# SEMAFORO.net
KiCad netlist of a schematic drawn in EAGLE
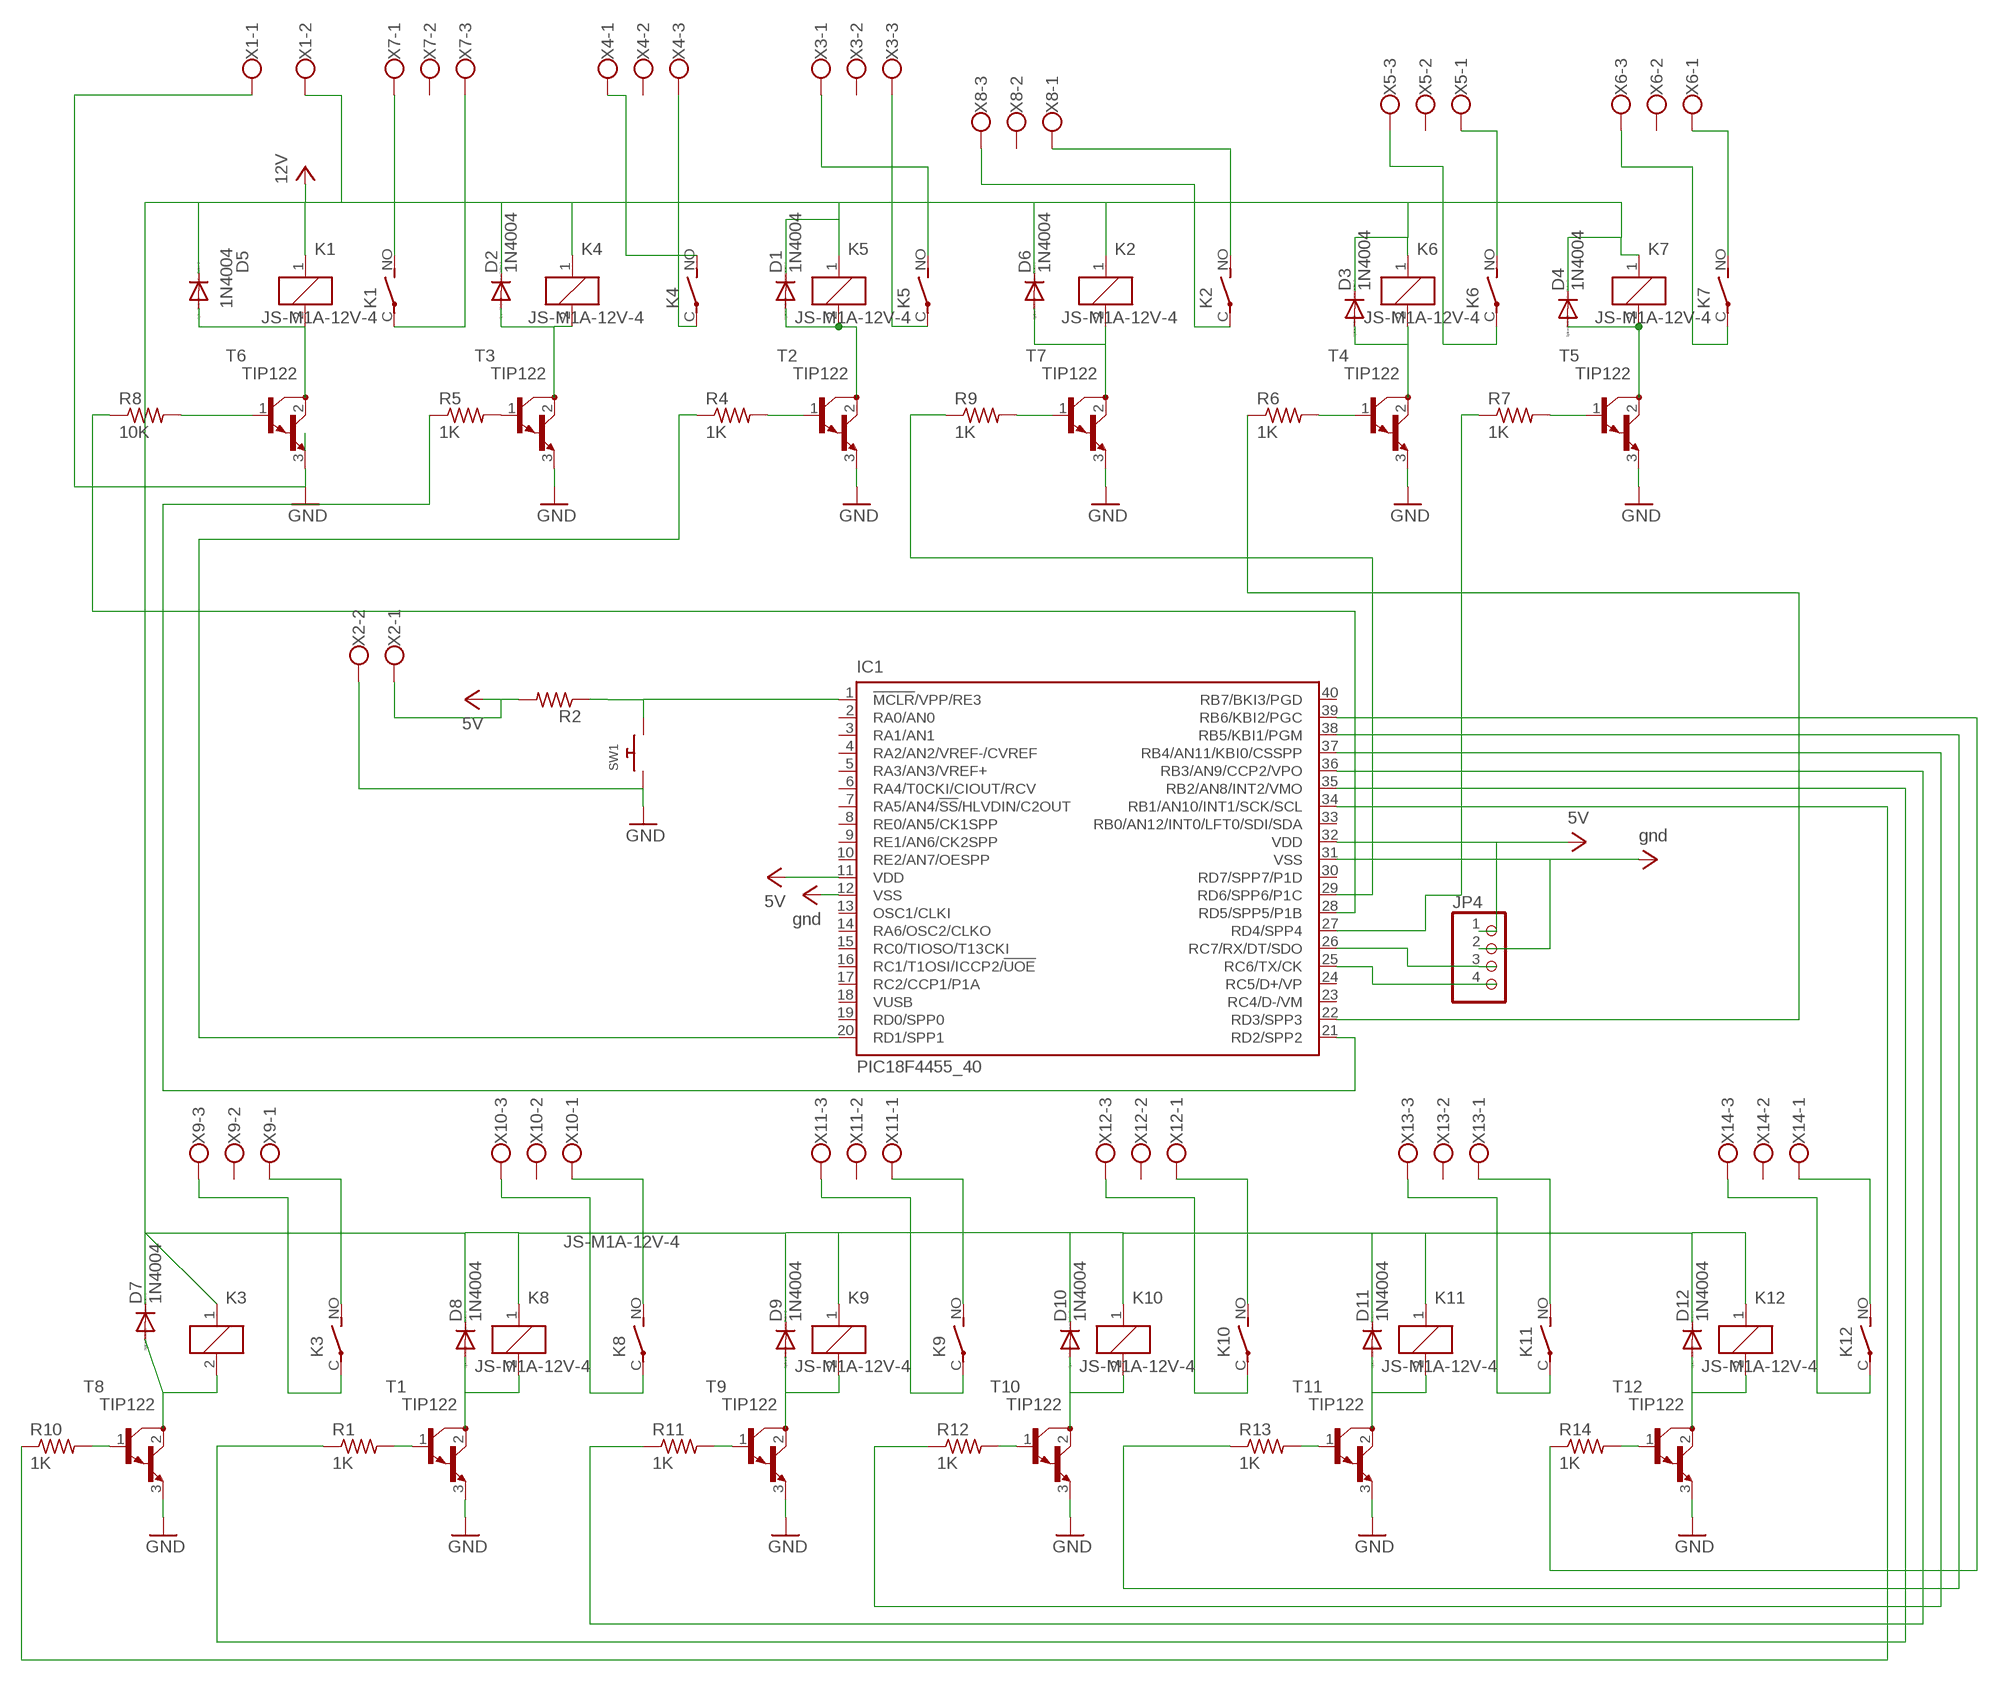
[diagram p0: schematic, sheet 1]

(export (version "E")
  (design (tool "Eeschema 10.0.6"))
  (components
    (comp (ref "D1")
      (value "1N4004")
      (footprint "eagle-import:DO41-10")
      (libsource (lib "eagle-import") (part "1N4004"))
    )
    (comp (ref "D2")
      (value "1N4004")
      (footprint "eagle-import:DO41-10")
      (libsource (lib "eagle-import") (part "1N4004"))
    )
    (comp (ref "D3")
      (value "1N4004")
      (footprint "eagle-import:DO41-10")
      (libsource (lib "eagle-import") (part "1N4004"))
    )
    (comp (ref "D4")
      (value "1N4004")
      (footprint "eagle-import:DO41-10")
      (libsource (lib "eagle-import") (part "1N4004"))
    )
    (comp (ref "D5")
      (value "1N4004")
      (footprint "eagle-import:DO41-10")
      (libsource (lib "eagle-import") (part "1N4004"))
    )
    (comp (ref "D6")
      (value "1N4004")
      (footprint "eagle-import:DO41-10")
      (libsource (lib "eagle-import") (part "1N4004"))
    )
    (comp (ref "D7")
      (value "1N4004")
      (footprint "eagle-import:DO41-10")
      (libsource (lib "eagle-import") (part "1N4004"))
    )
    (comp (ref "D8")
      (value "1N4004")
      (footprint "eagle-import:DO41-10")
      (libsource (lib "eagle-import") (part "1N4004"))
    )
    (comp (ref "D9")
      (value "1N4004")
      (footprint "eagle-import:DO41-10")
      (libsource (lib "eagle-import") (part "1N4004"))
    )
    (comp (ref "D10")
      (value "1N4004")
      (footprint "eagle-import:DO41-10")
      (libsource (lib "eagle-import") (part "1N4004"))
    )
    (comp (ref "D11")
      (value "1N4004")
      (footprint "eagle-import:DO41-10")
      (libsource (lib "eagle-import") (part "1N4004"))
    )
    (comp (ref "D12")
      (value "1N4004")
      (footprint "eagle-import:DO41-10")
      (libsource (lib "eagle-import") (part "1N4004"))
    )
    (comp (ref "IC1")
      (value "PIC18F4455_40")
      (footprint "eagle-import:DIL40")
      (fields (field (name "MF") "MICROCHIP") (field (name "MPN") "PIC18F4455-I/P"))
      (libsource (lib "eagle-import") (part "PIC18F4_40455"))
    )
    (comp (ref "JP4")
      (value "PINHD-1X4")
      (footprint "eagle-import:1X04")
      (libsource (lib "eagle-import") (part "PINHD-1X4"))
    )
    (comp (ref "K1")
      (value "JS-M1A-12V-4")
      (footprint "eagle-import:JS-M1A")
      (fields (field (name "MPN") "JSM1A-12V-4"))
      (libsource (lib "eagle-import") (part "JS-M1A-12V-4"))
    )
    (comp (ref "K2")
      (value "JS-M1A-12V-4")
      (footprint "eagle-import:JS-M1A")
      (fields (field (name "MPN") "JSM1A-12V-4"))
      (libsource (lib "eagle-import") (part "JS-M1A-12V-4"))
    )
    (comp (ref "K3")
      (value "JS-M1A-12V-4")
      (footprint "eagle-import:JS-M1A")
      (fields (field (name "MPN") "JSM1A-12V-4"))
      (libsource (lib "eagle-import") (part "JS-M1A-12V-4"))
    )
    (comp (ref "K4")
      (value "JS-M1A-12V-4")
      (footprint "eagle-import:JS-M1A")
      (fields (field (name "MPN") "JSM1A-12V-4"))
      (libsource (lib "eagle-import") (part "JS-M1A-12V-4"))
    )
    (comp (ref "K5")
      (value "JS-M1A-12V-4")
      (footprint "eagle-import:JS-M1A")
      (fields (field (name "MPN") "JSM1A-12V-4"))
      (libsource (lib "eagle-import") (part "JS-M1A-12V-4"))
    )
    (comp (ref "K6")
      (value "JS-M1A-12V-4")
      (footprint "eagle-import:JS-M1A")
      (fields (field (name "MPN") "JSM1A-12V-4"))
      (libsource (lib "eagle-import") (part "JS-M1A-12V-4"))
    )
    (comp (ref "K7")
      (value "JS-M1A-12V-4")
      (footprint "eagle-import:JS-M1A")
      (fields (field (name "MPN") "JSM1A-12V-4"))
      (libsource (lib "eagle-import") (part "JS-M1A-12V-4"))
    )
    (comp (ref "K8")
      (value "JS-M1A-12V-4")
      (footprint "eagle-import:JS-M1A")
      (fields (field (name "MPN") "JSM1A-12V-4"))
      (libsource (lib "eagle-import") (part "JS-M1A-12V-4"))
    )
    (comp (ref "K9")
      (value "JS-M1A-12V-4")
      (footprint "eagle-import:JS-M1A")
      (fields (field (name "MPN") "JSM1A-12V-4"))
      (libsource (lib "eagle-import") (part "JS-M1A-12V-4"))
    )
    (comp (ref "K10")
      (value "JS-M1A-12V-4")
      (footprint "eagle-import:JS-M1A")
      (fields (field (name "MPN") "JSM1A-12V-4"))
      (libsource (lib "eagle-import") (part "JS-M1A-12V-4"))
    )
    (comp (ref "K11")
      (value "JS-M1A-12V-4")
      (footprint "eagle-import:JS-M1A")
      (fields (field (name "MPN") "JSM1A-12V-4"))
      (libsource (lib "eagle-import") (part "JS-M1A-12V-4"))
    )
    (comp (ref "K12")
      (value "JS-M1A-12V-4")
      (footprint "eagle-import:JS-M1A")
      (fields (field (name "MPN") "JSM1A-12V-4"))
      (libsource (lib "eagle-import") (part "JS-M1A-12V-4"))
    )
    (comp (ref "R1")
      (value "1K")
      (footprint "eagle-import:0207_10")
      (libsource (lib "eagle-import") (part "R-US_0207/10"))
    )
    (comp (ref "R2")
      (value "R-US_0207/10")
      (footprint "eagle-import:0207_10")
      (libsource (lib "eagle-import") (part "R-US_0207/10"))
    )
    (comp (ref "R4")
      (value "1K")
      (footprint "eagle-import:0207_10")
      (libsource (lib "eagle-import") (part "R-US_0207/10"))
    )
    (comp (ref "R5")
      (value "1K")
      (footprint "eagle-import:0207_10")
      (libsource (lib "eagle-import") (part "R-US_0207/10"))
    )
    (comp (ref "R6")
      (value "1K")
      (footprint "eagle-import:0207_10")
      (libsource (lib "eagle-import") (part "R-US_0207/10"))
    )
    (comp (ref "R7")
      (value "1K")
      (footprint "eagle-import:0207_10")
      (libsource (lib "eagle-import") (part "R-US_0207/10"))
    )
    (comp (ref "R8")
      (value "10K")
      (footprint "eagle-import:0207_10")
      (libsource (lib "eagle-import") (part "R-US_0207/10"))
    )
    (comp (ref "R9")
      (value "1K")
      (footprint "eagle-import:0207_10")
      (libsource (lib "eagle-import") (part "R-US_0207/10"))
    )
    (comp (ref "R10")
      (value "1K")
      (footprint "eagle-import:0207_10")
      (libsource (lib "eagle-import") (part "R-US_0207/10"))
    )
    (comp (ref "R11")
      (value "1K")
      (footprint "eagle-import:0207_10")
      (libsource (lib "eagle-import") (part "R-US_0207/10"))
    )
    (comp (ref "R12")
      (value "1K")
      (footprint "eagle-import:0207_10")
      (libsource (lib "eagle-import") (part "R-US_0207/10"))
    )
    (comp (ref "R13")
      (value "1K")
      (footprint "eagle-import:0207_10")
      (libsource (lib "eagle-import") (part "R-US_0207/10"))
    )
    (comp (ref "R14")
      (value "1K")
      (footprint "eagle-import:0207_10")
      (libsource (lib "eagle-import") (part "R-US_0207/10"))
    )
    (comp (ref "SW1")
      (value "SWITCH_PUSHBUTTONEVQ-PE")
      (footprint "eagle-import:TACT_PANA-EVQ")
      (libsource (lib "eagle-import") (part "SWITCH_PUSHBUTTONEVQ-PE"))
    )
    (comp (ref "T1")
      (value "TIP122")
      (footprint "eagle-import:TO220")
      (libsource (lib "eagle-import") (part "TIP122"))
    )
    (comp (ref "T2")
      (value "TIP122")
      (footprint "eagle-import:TO220")
      (libsource (lib "eagle-import") (part "TIP122"))
    )
    (comp (ref "T3")
      (value "TIP122")
      (footprint "eagle-import:TO220")
      (libsource (lib "eagle-import") (part "TIP122"))
    )
    (comp (ref "T4")
      (value "TIP122")
      (footprint "eagle-import:TO220")
      (libsource (lib "eagle-import") (part "TIP122"))
    )
    (comp (ref "T5")
      (value "TIP122")
      (footprint "eagle-import:TO220")
      (libsource (lib "eagle-import") (part "TIP122"))
    )
    (comp (ref "T6")
      (value "TIP122")
      (footprint "eagle-import:TO220")
      (libsource (lib "eagle-import") (part "TIP122"))
    )
    (comp (ref "T7")
      (value "TIP122")
      (footprint "eagle-import:TO220")
      (libsource (lib "eagle-import") (part "TIP122"))
    )
    (comp (ref "T8")
      (value "TIP122")
      (footprint "eagle-import:TO220")
      (libsource (lib "eagle-import") (part "TIP122"))
    )
    (comp (ref "T9")
      (value "TIP122")
      (footprint "eagle-import:TO220")
      (libsource (lib "eagle-import") (part "TIP122"))
    )
    (comp (ref "T10")
      (value "TIP122")
      (footprint "eagle-import:TO220")
      (libsource (lib "eagle-import") (part "TIP122"))
    )
    (comp (ref "T11")
      (value "TIP122")
      (footprint "eagle-import:TO220")
      (libsource (lib "eagle-import") (part "TIP122"))
    )
    (comp (ref "T12")
      (value "TIP122")
      (footprint "eagle-import:TO220")
      (libsource (lib "eagle-import") (part "TIP122"))
    )
    (comp (ref "X1")
      (value "W237-102")
      (footprint "eagle-import:W237-102")
      (fields (field (name "MPN") "237-102"))
      (libsource (lib "eagle-import") (part "W237-102"))
    )
    (comp (ref "X2")
      (value "W237-102")
      (footprint "eagle-import:W237-102")
      (fields (field (name "MPN") "237-102"))
      (libsource (lib "eagle-import") (part "W237-102"))
    )
    (comp (ref "X3")
      (value "W237-103")
      (footprint "eagle-import:W237-103")
      (fields (field (name "MPN") "237-103"))
      (libsource (lib "eagle-import") (part "W237-103"))
    )
    (comp (ref "X4")
      (value "W237-103")
      (footprint "eagle-import:W237-103")
      (fields (field (name "MPN") "237-103"))
      (libsource (lib "eagle-import") (part "W237-103"))
    )
    (comp (ref "X5")
      (value "W237-103")
      (footprint "eagle-import:W237-103")
      (fields (field (name "MPN") "237-103"))
      (libsource (lib "eagle-import") (part "W237-103"))
    )
    (comp (ref "X6")
      (value "W237-103")
      (footprint "eagle-import:W237-103")
      (fields (field (name "MPN") "237-103"))
      (libsource (lib "eagle-import") (part "W237-103"))
    )
    (comp (ref "X7")
      (value "W237-103")
      (footprint "eagle-import:W237-103")
      (fields (field (name "MPN") "237-103"))
      (libsource (lib "eagle-import") (part "W237-103"))
    )
    (comp (ref "X8")
      (value "W237-103")
      (footprint "eagle-import:W237-103")
      (fields (field (name "MPN") "237-103"))
      (libsource (lib "eagle-import") (part "W237-103"))
    )
    (comp (ref "X9")
      (value "W237-103")
      (footprint "eagle-import:W237-103")
      (fields (field (name "MPN") "237-103"))
      (libsource (lib "eagle-import") (part "W237-103"))
    )
    (comp (ref "X10")
      (value "W237-103")
      (footprint "eagle-import:W237-103")
      (fields (field (name "MPN") "237-103"))
      (libsource (lib "eagle-import") (part "W237-103"))
    )
    (comp (ref "X11")
      (value "W237-103")
      (footprint "eagle-import:W237-103")
      (fields (field (name "MPN") "237-103"))
      (libsource (lib "eagle-import") (part "W237-103"))
    )
    (comp (ref "X12")
      (value "W237-103")
      (footprint "eagle-import:W237-103")
      (fields (field (name "MPN") "237-103"))
      (libsource (lib "eagle-import") (part "W237-103"))
    )
    (comp (ref "X13")
      (value "W237-103")
      (footprint "eagle-import:W237-103")
      (fields (field (name "MPN") "237-103"))
      (libsource (lib "eagle-import") (part "W237-103"))
    )
    (comp (ref "X14")
      (value "W237-103")
      (footprint "eagle-import:W237-103")
      (fields (field (name "MPN") "237-103"))
      (libsource (lib "eagle-import") (part "W237-103"))
    )
  )
  (nets
    (net (code "1") (name "5V") (class "Default")
      (node (ref "IC1") (pin "11") (pinfunction "VDD_11") (pintype "power_in"))
      (node (ref "IC1") (pin "32") (pinfunction "VDD_32") (pintype "power_in"))
      (node (ref "JP4") (pin "1") (pinfunction "1_1") (pintype "passive"))
      (node (ref "R2") (pin "2") (pinfunction "2_2") (pintype "passive"))
      (node (ref "X2") (pin "1") (pinfunction "KL_1") (pintype "passive"))
    )
    (net (code "2") (name "12V") (class "Default")
      (node (ref "D1") (pin "C") (pinfunction "C_C") (pintype "passive"))
      (node (ref "D10") (pin "C") (pinfunction "C_C") (pintype "passive"))
      (node (ref "D11") (pin "C") (pinfunction "C_C") (pintype "passive"))
      (node (ref "D12") (pin "C") (pinfunction "C_C") (pintype "passive"))
      (node (ref "D2") (pin "C") (pinfunction "C_C") (pintype "passive"))
      (node (ref "D3") (pin "C") (pinfunction "C_C") (pintype "passive"))
      (node (ref "D4") (pin "C") (pinfunction "C_C") (pintype "passive"))
      (node (ref "D5") (pin "C") (pinfunction "C_C") (pintype "passive"))
      (node (ref "D6") (pin "C") (pinfunction "C_C") (pintype "passive"))
      (node (ref "D7") (pin "C") (pinfunction "C_C") (pintype "passive"))
      (node (ref "D8") (pin "C") (pinfunction "C_C") (pintype "passive"))
      (node (ref "D9") (pin "C") (pinfunction "C_C") (pintype "passive"))
      (node (ref "K1") (pin "1") (pinfunction "1_1") (pintype "passive"))
      (node (ref "K10") (pin "1") (pinfunction "1_1") (pintype "passive"))
      (node (ref "K11") (pin "1") (pinfunction "1_1") (pintype "passive"))
      (node (ref "K12") (pin "1") (pinfunction "1_1") (pintype "passive"))
      (node (ref "K2") (pin "1") (pinfunction "1_1") (pintype "passive"))
      (node (ref "K3") (pin "1") (pinfunction "1_1") (pintype "passive"))
      (node (ref "K4") (pin "1") (pinfunction "1_1") (pintype "passive"))
      (node (ref "K5") (pin "1") (pinfunction "1_1") (pintype "passive"))
      (node (ref "K6") (pin "1") (pinfunction "1_1") (pintype "passive"))
      (node (ref "K7") (pin "1") (pinfunction "1_1") (pintype "passive"))
      (node (ref "K8") (pin "1") (pinfunction "1_1") (pintype "passive"))
      (node (ref "K9") (pin "1") (pinfunction "1_1") (pintype "passive"))
      (node (ref "X1") (pin "2") (pinfunction "KL_2") (pintype "passive"))
    )
    (net (code "3") (name "GND") (class "Default")
      (node (ref "IC1") (pin "12") (pinfunction "VSS_12") (pintype "power_in"))
      (node (ref "IC1") (pin "31") (pinfunction "VSS_31") (pintype "power_in"))
      (node (ref "JP4") (pin "2") (pinfunction "2_2") (pintype "passive"))
      (node (ref "SW1") (pin "P$1") (pinfunction "P$1_P$1") (pintype "passive"))
      (node (ref "T1") (pin "3") (pinfunction "E_3") (pintype "passive"))
      (node (ref "T10") (pin "3") (pinfunction "E_3") (pintype "passive"))
      (node (ref "T11") (pin "3") (pinfunction "E_3") (pintype "passive"))
      (node (ref "T12") (pin "3") (pinfunction "E_3") (pintype "passive"))
      (node (ref "T2") (pin "3") (pinfunction "E_3") (pintype "passive"))
      (node (ref "T3") (pin "3") (pinfunction "E_3") (pintype "passive"))
      (node (ref "T4") (pin "3") (pinfunction "E_3") (pintype "passive"))
      (node (ref "T5") (pin "3") (pinfunction "E_3") (pintype "passive"))
      (node (ref "T6") (pin "3") (pinfunction "E_3") (pintype "passive"))
      (node (ref "T7") (pin "3") (pinfunction "E_3") (pintype "passive"))
      (node (ref "T8") (pin "3") (pinfunction "E_3") (pintype "passive"))
      (node (ref "T9") (pin "3") (pinfunction "E_3") (pintype "passive"))
      (node (ref "X1") (pin "1") (pinfunction "KL_1") (pintype "passive"))
      (node (ref "X2") (pin "2") (pinfunction "KL_2") (pintype "passive"))
    )
    (net (code "4") (name "Net-(IC1-RB1{slash}AN10{slash}INT1{slash}SCK{slash}SCL)") (class "Default")
      (node (ref "IC1") (pin "34") (pinfunction "RB1/AN10/INT1/SCK/SCL_34") (pintype "bidirectional"))
      (node (ref "R10") (pin "1") (pinfunction "1_1") (pintype "passive"))
    )
    (net (code "5") (name "Net-(IC1-RB2{slash}AN8{slash}INT2{slash}VMO)") (class "Default")
      (node (ref "IC1") (pin "35") (pinfunction "RB2/AN8/INT2/VMO_35") (pintype "bidirectional"))
      (node (ref "R1") (pin "1") (pinfunction "1_1") (pintype "passive"))
    )
    (net (code "6") (name "Net-(IC1-RB3{slash}AN9{slash}CCP2{slash}VPO)") (class "Default")
      (node (ref "IC1") (pin "36") (pinfunction "RB3/AN9/CCP2/VPO_36") (pintype "bidirectional"))
      (node (ref "R11") (pin "1") (pinfunction "1_1") (pintype "passive"))
    )
    (net (code "7") (name "Net-(IC1-RB4{slash}AN11{slash}KBI0{slash}CSSPP)") (class "Default")
      (node (ref "IC1") (pin "37") (pinfunction "RB4/AN11/KBI0/CSSPP_37") (pintype "bidirectional"))
      (node (ref "R12") (pin "1") (pinfunction "1_1") (pintype "passive"))
    )
    (net (code "8") (name "Net-(IC1-RB5{slash}KBI1{slash}PGM)") (class "Default")
      (node (ref "IC1") (pin "38") (pinfunction "RB5/KBI1/PGM_38") (pintype "bidirectional"))
      (node (ref "R13") (pin "1") (pinfunction "1_1") (pintype "passive"))
    )
    (net (code "9") (name "Net-(IC1-RB6{slash}KBI2{slash}PGC)") (class "Default")
      (node (ref "IC1") (pin "39") (pinfunction "RB6/KBI2/PGC_39") (pintype "bidirectional"))
      (node (ref "R14") (pin "1") (pinfunction "1_1") (pintype "passive"))
    )
    (net (code "10") (name "Net-(IC1-RC6{slash}TX{slash}CK)") (class "Default")
      (node (ref "IC1") (pin "25") (pinfunction "RC6/TX/CK_25") (pintype "bidirectional"))
      (node (ref "JP4") (pin "4") (pinfunction "4_4") (pintype "passive"))
    )
    (net (code "11") (name "Net-(IC1-RC7{slash}RX{slash}DT{slash}SDO)") (class "Default")
      (node (ref "IC1") (pin "26") (pinfunction "RC7/RX/DT/SDO_26") (pintype "bidirectional"))
      (node (ref "JP4") (pin "3") (pinfunction "3_3") (pintype "passive"))
    )
    (net (code "12") (name "Net-(IC1-RD1{slash}SPP1)") (class "Default")
      (node (ref "IC1") (pin "20") (pinfunction "RD1/SPP1_20") (pintype "bidirectional"))
      (node (ref "R4") (pin "1") (pinfunction "1_1") (pintype "passive"))
    )
    (net (code "13") (name "Net-(IC1-RD2{slash}SPP2)") (class "Default")
      (node (ref "IC1") (pin "21") (pinfunction "RD2/SPP2_21") (pintype "bidirectional"))
      (node (ref "R5") (pin "1") (pinfunction "1_1") (pintype "passive"))
    )
    (net (code "14") (name "Net-(IC1-RD3{slash}SPP3)") (class "Default")
      (node (ref "IC1") (pin "22") (pinfunction "RD3/SPP3_22") (pintype "bidirectional"))
      (node (ref "R6") (pin "1") (pinfunction "1_1") (pintype "passive"))
    )
    (net (code "15") (name "Net-(IC1-RD4{slash}SPP4)") (class "Default")
      (node (ref "IC1") (pin "27") (pinfunction "RD4/SPP4_27") (pintype "bidirectional"))
      (node (ref "R7") (pin "1") (pinfunction "1_1") (pintype "passive"))
    )
    (net (code "16") (name "Net-(IC1-RD5{slash}SPP5{slash}P1B)") (class "Default")
      (node (ref "IC1") (pin "28") (pinfunction "RD5/SPP5/P1B_28") (pintype "bidirectional"))
      (node (ref "R8") (pin "1") (pinfunction "1_1") (pintype "passive"))
    )
    (net (code "17") (name "Net-(IC1-RD6{slash}SPP6{slash}P1C)") (class "Default")
      (node (ref "IC1") (pin "29") (pinfunction "RD6/SPP6/P1C_29") (pintype "bidirectional"))
      (node (ref "R9") (pin "1") (pinfunction "1_1") (pintype "passive"))
    )
    (net (code "18") (name "Net-(IC1-~{MCLR}{slash}VPP{slash}RE3)") (class "Default")
      (node (ref "IC1") (pin "1") (pinfunction "~{MCLR}/VPP/RE3_1") (pintype "input"))
      (node (ref "R2") (pin "1") (pinfunction "1_1") (pintype "passive"))
      (node (ref "SW1") (pin "P$2") (pinfunction "P$2_P$2") (pintype "passive"))
    )
    (net (code "19") (name "Net-(K1B-P)") (class "Default")
      (node (ref "K1") (pin "C") (pinfunction "P_C") (pintype "passive"))
      (node (ref "X7") (pin "3") (pinfunction "KL_3") (pintype "passive"))
    )
    (net (code "20") (name "Net-(K1B-S)") (class "Default")
      (node (ref "K1") (pin "NO") (pinfunction "S_NO") (pintype "passive"))
      (node (ref "X7") (pin "1") (pinfunction "KL_1") (pintype "passive"))
    )
    (net (code "21") (name "Net-(K2B-P)") (class "Default")
      (node (ref "K2") (pin "C") (pinfunction "P_C") (pintype "passive"))
      (node (ref "X8") (pin "3") (pinfunction "KL_3") (pintype "passive"))
    )
    (net (code "22") (name "Net-(K2B-S)") (class "Default")
      (node (ref "K2") (pin "NO") (pinfunction "S_NO") (pintype "passive"))
      (node (ref "X8") (pin "1") (pinfunction "KL_1") (pintype "passive"))
    )
    (net (code "23") (name "Net-(K3B-P)") (class "Default")
      (node (ref "K3") (pin "C") (pinfunction "P_C") (pintype "passive"))
      (node (ref "X9") (pin "3") (pinfunction "KL_3") (pintype "passive"))
    )
    (net (code "24") (name "Net-(K3B-S)") (class "Default")
      (node (ref "K3") (pin "NO") (pinfunction "S_NO") (pintype "passive"))
      (node (ref "X9") (pin "1") (pinfunction "KL_1") (pintype "passive"))
    )
    (net (code "25") (name "Net-(K4B-P)") (class "Default")
      (node (ref "K4") (pin "C") (pinfunction "P_C") (pintype "passive"))
      (node (ref "X4") (pin "3") (pinfunction "KL_3") (pintype "passive"))
    )
    (net (code "26") (name "Net-(K4B-S)") (class "Default")
      (node (ref "K4") (pin "NO") (pinfunction "S_NO") (pintype "passive"))
      (node (ref "X4") (pin "1") (pinfunction "KL_1") (pintype "passive"))
    )
    (net (code "27") (name "Net-(K5B-P)") (class "Default")
      (node (ref "K5") (pin "C") (pinfunction "P_C") (pintype "passive"))
      (node (ref "X3") (pin "3") (pinfunction "KL_3") (pintype "passive"))
    )
    (net (code "28") (name "Net-(K5B-S)") (class "Default")
      (node (ref "K5") (pin "NO") (pinfunction "S_NO") (pintype "passive"))
      (node (ref "X3") (pin "1") (pinfunction "KL_1") (pintype "passive"))
    )
    (net (code "29") (name "Net-(K6B-P)") (class "Default")
      (node (ref "K6") (pin "C") (pinfunction "P_C") (pintype "passive"))
      (node (ref "X5") (pin "3") (pinfunction "KL_3") (pintype "passive"))
    )
    (net (code "30") (name "Net-(K6B-S)") (class "Default")
      (node (ref "K6") (pin "NO") (pinfunction "S_NO") (pintype "passive"))
      (node (ref "X5") (pin "1") (pinfunction "KL_1") (pintype "passive"))
    )
    (net (code "31") (name "Net-(K7B-P)") (class "Default")
      (node (ref "K7") (pin "C") (pinfunction "P_C") (pintype "passive"))
      (node (ref "X6") (pin "3") (pinfunction "KL_3") (pintype "passive"))
    )
    (net (code "32") (name "Net-(K7B-S)") (class "Default")
      (node (ref "K7") (pin "NO") (pinfunction "S_NO") (pintype "passive"))
      (node (ref "X6") (pin "1") (pinfunction "KL_1") (pintype "passive"))
    )
    (net (code "33") (name "Net-(K8B-P)") (class "Default")
      (node (ref "K8") (pin "C") (pinfunction "P_C") (pintype "passive"))
      (node (ref "X10") (pin "3") (pinfunction "KL_3") (pintype "passive"))
    )
    (net (code "34") (name "Net-(K8B-S)") (class "Default")
      (node (ref "K8") (pin "NO") (pinfunction "S_NO") (pintype "passive"))
      (node (ref "X10") (pin "1") (pinfunction "KL_1") (pintype "passive"))
    )
    (net (code "35") (name "Net-(K9B-P)") (class "Default")
      (node (ref "K9") (pin "C") (pinfunction "P_C") (pintype "passive"))
      (node (ref "X11") (pin "3") (pinfunction "KL_3") (pintype "passive"))
    )
    (net (code "36") (name "Net-(K9B-S)") (class "Default")
      (node (ref "K9") (pin "NO") (pinfunction "S_NO") (pintype "passive"))
      (node (ref "X11") (pin "1") (pinfunction "KL_1") (pintype "passive"))
    )
    (net (code "37") (name "Net-(K10B-P)") (class "Default")
      (node (ref "K10") (pin "C") (pinfunction "P_C") (pintype "passive"))
      (node (ref "X12") (pin "3") (pinfunction "KL_3") (pintype "passive"))
    )
    (net (code "38") (name "Net-(K10B-S)") (class "Default")
      (node (ref "K10") (pin "NO") (pinfunction "S_NO") (pintype "passive"))
      (node (ref "X12") (pin "1") (pinfunction "KL_1") (pintype "passive"))
    )
    (net (code "39") (name "Net-(K11B-P)") (class "Default")
      (node (ref "K11") (pin "C") (pinfunction "P_C") (pintype "passive"))
      (node (ref "X13") (pin "3") (pinfunction "KL_3") (pintype "passive"))
    )
    (net (code "40") (name "Net-(K11B-S)") (class "Default")
      (node (ref "K11") (pin "NO") (pinfunction "S_NO") (pintype "passive"))
      (node (ref "X13") (pin "1") (pinfunction "KL_1") (pintype "passive"))
    )
    (net (code "41") (name "Net-(K12B-P)") (class "Default")
      (node (ref "K12") (pin "C") (pinfunction "P_C") (pintype "passive"))
      (node (ref "X14") (pin "3") (pinfunction "KL_3") (pintype "passive"))
    )
    (net (code "42") (name "Net-(K12B-S)") (class "Default")
      (node (ref "K12") (pin "NO") (pinfunction "S_NO") (pintype "passive"))
      (node (ref "X14") (pin "1") (pinfunction "KL_1") (pintype "passive"))
    )
    (net (code "43") (name "Net-(T1-B)") (class "Default")
      (node (ref "R1") (pin "2") (pinfunction "2_2") (pintype "passive"))
      (node (ref "T1") (pin "1") (pinfunction "B_1") (pintype "passive"))
    )
    (net (code "44") (name "Net-(T1-C)") (class "Default")
      (node (ref "D8") (pin "A") (pinfunction "A_A") (pintype "passive"))
      (node (ref "K8") (pin "2") (pinfunction "2_2") (pintype "passive"))
      (node (ref "T1") (pin "2") (pinfunction "C_2") (pintype "passive"))
    )
    (net (code "45") (name "Net-(T2-B)") (class "Default")
      (node (ref "R4") (pin "2") (pinfunction "2_2") (pintype "passive"))
      (node (ref "T2") (pin "1") (pinfunction "B_1") (pintype "passive"))
    )
    (net (code "46") (name "Net-(T2-C)") (class "Default")
      (node (ref "D1") (pin "A") (pinfunction "A_A") (pintype "passive"))
      (node (ref "K5") (pin "2") (pinfunction "2_2") (pintype "passive"))
      (node (ref "T2") (pin "2") (pinfunction "C_2") (pintype "passive"))
    )
    (net (code "47") (name "Net-(T3-B)") (class "Default")
      (node (ref "R5") (pin "2") (pinfunction "2_2") (pintype "passive"))
      (node (ref "T3") (pin "1") (pinfunction "B_1") (pintype "passive"))
    )
    (net (code "48") (name "Net-(T3-C)") (class "Default")
      (node (ref "D2") (pin "A") (pinfunction "A_A") (pintype "passive"))
      (node (ref "K4") (pin "2") (pinfunction "2_2") (pintype "passive"))
      (node (ref "T3") (pin "2") (pinfunction "C_2") (pintype "passive"))
    )
    (net (code "49") (name "Net-(T4-B)") (class "Default")
      (node (ref "R6") (pin "2") (pinfunction "2_2") (pintype "passive"))
      (node (ref "T4") (pin "1") (pinfunction "B_1") (pintype "passive"))
    )
    (net (code "50") (name "Net-(T4-C)") (class "Default")
      (node (ref "D3") (pin "A") (pinfunction "A_A") (pintype "passive"))
      (node (ref "K6") (pin "2") (pinfunction "2_2") (pintype "passive"))
      (node (ref "T4") (pin "2") (pinfunction "C_2") (pintype "passive"))
    )
    (net (code "51") (name "Net-(T5-B)") (class "Default")
      (node (ref "R7") (pin "2") (pinfunction "2_2") (pintype "passive"))
      (node (ref "T5") (pin "1") (pinfunction "B_1") (pintype "passive"))
    )
    (net (code "52") (name "Net-(T5-C)") (class "Default")
      (node (ref "D4") (pin "A") (pinfunction "A_A") (pintype "passive"))
      (node (ref "K7") (pin "2") (pinfunction "2_2") (pintype "passive"))
      (node (ref "T5") (pin "2") (pinfunction "C_2") (pintype "passive"))
    )
    (net (code "53") (name "Net-(T6-B)") (class "Default")
      (node (ref "R8") (pin "2") (pinfunction "2_2") (pintype "passive"))
      (node (ref "T6") (pin "1") (pinfunction "B_1") (pintype "passive"))
    )
    (net (code "54") (name "Net-(T6-C)") (class "Default")
      (node (ref "D5") (pin "A") (pinfunction "A_A") (pintype "passive"))
      (node (ref "K1") (pin "2") (pinfunction "2_2") (pintype "passive"))
      (node (ref "T6") (pin "2") (pinfunction "C_2") (pintype "passive"))
    )
    (net (code "55") (name "Net-(T7-B)") (class "Default")
      (node (ref "R9") (pin "2") (pinfunction "2_2") (pintype "passive"))
      (node (ref "T7") (pin "1") (pinfunction "B_1") (pintype "passive"))
    )
    (net (code "56") (name "Net-(T7-C)") (class "Default")
      (node (ref "D6") (pin "A") (pinfunction "A_A") (pintype "passive"))
      (node (ref "K2") (pin "2") (pinfunction "2_2") (pintype "passive"))
      (node (ref "T7") (pin "2") (pinfunction "C_2") (pintype "passive"))
    )
    (net (code "57") (name "Net-(T8-B)") (class "Default")
      (node (ref "R10") (pin "2") (pinfunction "2_2") (pintype "passive"))
      (node (ref "T8") (pin "1") (pinfunction "B_1") (pintype "passive"))
    )
    (net (code "58") (name "Net-(T8-C)") (class "Default")
      (node (ref "D7") (pin "A") (pinfunction "A_A") (pintype "passive"))
      (node (ref "K3") (pin "2") (pinfunction "2_2") (pintype "passive"))
      (node (ref "T8") (pin "2") (pinfunction "C_2") (pintype "passive"))
    )
    (net (code "59") (name "Net-(T9-B)") (class "Default")
      (node (ref "R11") (pin "2") (pinfunction "2_2") (pintype "passive"))
      (node (ref "T9") (pin "1") (pinfunction "B_1") (pintype "passive"))
    )
    (net (code "60") (name "Net-(T9-C)") (class "Default")
      (node (ref "D9") (pin "A") (pinfunction "A_A") (pintype "passive"))
      (node (ref "K9") (pin "2") (pinfunction "2_2") (pintype "passive"))
      (node (ref "T9") (pin "2") (pinfunction "C_2") (pintype "passive"))
    )
    (net (code "61") (name "Net-(T10-B)") (class "Default")
      (node (ref "R12") (pin "2") (pinfunction "2_2") (pintype "passive"))
      (node (ref "T10") (pin "1") (pinfunction "B_1") (pintype "passive"))
    )
    (net (code "62") (name "Net-(T10-C)") (class "Default")
      (node (ref "D10") (pin "A") (pinfunction "A_A") (pintype "passive"))
      (node (ref "K10") (pin "2") (pinfunction "2_2") (pintype "passive"))
      (node (ref "T10") (pin "2") (pinfunction "C_2") (pintype "passive"))
    )
    (net (code "63") (name "Net-(T11-B)") (class "Default")
      (node (ref "R13") (pin "2") (pinfunction "2_2") (pintype "passive"))
      (node (ref "T11") (pin "1") (pinfunction "B_1") (pintype "passive"))
    )
    (net (code "64") (name "Net-(T11-C)") (class "Default")
      (node (ref "D11") (pin "A") (pinfunction "A_A") (pintype "passive"))
      (node (ref "K11") (pin "2") (pinfunction "2_2") (pintype "passive"))
      (node (ref "T11") (pin "2") (pinfunction "C_2") (pintype "passive"))
    )
    (net (code "65") (name "Net-(T12-B)") (class "Default")
      (node (ref "R14") (pin "2") (pinfunction "2_2") (pintype "passive"))
      (node (ref "T12") (pin "1") (pinfunction "B_1") (pintype "passive"))
    )
    (net (code "66") (name "Net-(T12-C)") (class "Default")
      (node (ref "D12") (pin "A") (pinfunction "A_A") (pintype "passive"))
      (node (ref "K12") (pin "2") (pinfunction "2_2") (pintype "passive"))
      (node (ref "T12") (pin "2") (pinfunction "C_2") (pintype "passive"))
    )
    (net (code "67") (name "unconnected-(IC1-OSC1{slash}CLKI-Pad13)") (class "Default")
      (node (ref "IC1") (pin "13") (pinfunction "OSC1/CLKI_13") (pintype "input"))
    )
    (net (code "68") (name "unconnected-(IC1-RA0{slash}AN0-Pad2)") (class "Default")
      (node (ref "IC1") (pin "2") (pinfunction "RA0/AN0_2") (pintype "bidirectional"))
    )
    (net (code "69") (name "unconnected-(IC1-RA1{slash}AN1-Pad3)") (class "Default")
      (node (ref "IC1") (pin "3") (pinfunction "RA1/AN1_3") (pintype "bidirectional"))
    )
    (net (code "70") (name "unconnected-(IC1-RA2{slash}AN2{slash}VREF-{slash}CVREF-Pad4)") (class "Default")
      (node (ref "IC1") (pin "4") (pinfunction "RA2/AN2/VREF-/CVREF_4") (pintype "bidirectional"))
    )
    (net (code "71") (name "unconnected-(IC1-RA3{slash}AN3{slash}VREF+-Pad5)") (class "Default")
      (node (ref "IC1") (pin "5") (pinfunction "RA3/AN3/VREF+_5") (pintype "bidirectional"))
    )
    (net (code "72") (name "unconnected-(IC1-RA4{slash}T0CKI{slash}CIOUT{slash}RCV-Pad6)") (class "Default")
      (node (ref "IC1") (pin "6") (pinfunction "RA4/T0CKI/CIOUT/RCV_6") (pintype "bidirectional"))
    )
    (net (code "73") (name "unconnected-(IC1-RA5{slash}AN4{slash}~{SS}{slash}HLVDIN{slash}C2OUT-Pad7)") (class "Default")
      (node (ref "IC1") (pin "7") (pinfunction "RA5/AN4/~{SS}/HLVDIN/C2OUT_7") (pintype "bidirectional"))
    )
    (net (code "74") (name "unconnected-(IC1-RA6{slash}OSC2{slash}CLKO-Pad14)") (class "Default")
      (node (ref "IC1") (pin "14") (pinfunction "RA6/OSC2/CLKO_14") (pintype "output"))
    )
    (net (code "75") (name "unconnected-(IC1-RB0{slash}AN12{slash}INT0{slash}LFT0{slash}SDI{slash}SDA-Pad33)") (class "Default")
      (node (ref "IC1") (pin "33") (pinfunction "RB0/AN12/INT0/LFT0/SDI/SDA_33") (pintype "bidirectional"))
    )
    (net (code "76") (name "unconnected-(IC1-RB7{slash}BKI3{slash}PGD-Pad40)") (class "Default")
      (node (ref "IC1") (pin "40") (pinfunction "RB7/BKI3/PGD_40") (pintype "bidirectional"))
    )
    (net (code "77") (name "unconnected-(IC1-RC0{slash}TIOSO{slash}T13CKI-Pad15)") (class "Default")
      (node (ref "IC1") (pin "15") (pinfunction "RC0/TIOSO/T13CKI_15") (pintype "bidirectional"))
    )
    (net (code "78") (name "unconnected-(IC1-RC1{slash}T1OSI{slash}ICCP2{slash}~{UOE}-Pad16)") (class "Default")
      (node (ref "IC1") (pin "16") (pinfunction "RC1/T1OSI/ICCP2/~{UOE}_16") (pintype "bidirectional"))
    )
    (net (code "79") (name "unconnected-(IC1-RC2{slash}CCP1{slash}P1A-Pad17)") (class "Default")
      (node (ref "IC1") (pin "17") (pinfunction "RC2/CCP1/P1A_17") (pintype "bidirectional"))
    )
    (net (code "80") (name "unconnected-(IC1-RC4{slash}D-{slash}VM-Pad23)") (class "Default")
      (node (ref "IC1") (pin "23") (pinfunction "RC4/D-/VM_23") (pintype "bidirectional"))
    )
    (net (code "81") (name "unconnected-(IC1-RC5{slash}D+{slash}VP-Pad24)") (class "Default")
      (node (ref "IC1") (pin "24") (pinfunction "RC5/D+/VP_24") (pintype "bidirectional"))
    )
    (net (code "82") (name "unconnected-(IC1-RD0{slash}SPP0-Pad19)") (class "Default")
      (node (ref "IC1") (pin "19") (pinfunction "RD0/SPP0_19") (pintype "bidirectional"))
    )
    (net (code "83") (name "unconnected-(IC1-RD7{slash}SPP7{slash}P1D-Pad30)") (class "Default")
      (node (ref "IC1") (pin "30") (pinfunction "RD7/SPP7/P1D_30") (pintype "bidirectional"))
    )
    (net (code "84") (name "unconnected-(IC1-RE0{slash}AN5{slash}CK1SPP-Pad8)") (class "Default")
      (node (ref "IC1") (pin "8") (pinfunction "RE0/AN5/CK1SPP_8") (pintype "bidirectional"))
    )
    (net (code "85") (name "unconnected-(IC1-RE1{slash}AN6{slash}CK2SPP-Pad9)") (class "Default")
      (node (ref "IC1") (pin "9") (pinfunction "RE1/AN6/CK2SPP_9") (pintype "bidirectional"))
    )
    (net (code "86") (name "unconnected-(IC1-RE2{slash}AN7{slash}OESPP-Pad10)") (class "Default")
      (node (ref "IC1") (pin "10") (pinfunction "RE2/AN7/OESPP_10") (pintype "bidirectional"))
    )
    (net (code "87") (name "unconnected-(IC1-VUSB-Pad18)") (class "Default")
      (node (ref "IC1") (pin "18") (pinfunction "VUSB_18") (pintype "bidirectional"))
    )
    (net (code "88") (name "unconnected-(X3B-KL-Pad2)") (class "Default")
      (node (ref "X3") (pin "2") (pinfunction "KL_2") (pintype "passive"))
    )
    (net (code "89") (name "unconnected-(X4B-KL-Pad2)") (class "Default")
      (node (ref "X4") (pin "2") (pinfunction "KL_2") (pintype "passive"))
    )
    (net (code "90") (name "unconnected-(X5B-KL-Pad2)") (class "Default")
      (node (ref "X5") (pin "2") (pinfunction "KL_2") (pintype "passive"))
    )
    (net (code "91") (name "unconnected-(X6B-KL-Pad2)") (class "Default")
      (node (ref "X6") (pin "2") (pinfunction "KL_2") (pintype "passive"))
    )
    (net (code "92") (name "unconnected-(X7B-KL-Pad2)") (class "Default")
      (node (ref "X7") (pin "2") (pinfunction "KL_2") (pintype "passive"))
    )
    (net (code "93") (name "unconnected-(X8B-KL-Pad2)") (class "Default")
      (node (ref "X8") (pin "2") (pinfunction "KL_2") (pintype "passive"))
    )
    (net (code "94") (name "unconnected-(X9B-KL-Pad2)") (class "Default")
      (node (ref "X9") (pin "2") (pinfunction "KL_2") (pintype "passive"))
    )
    (net (code "95") (name "unconnected-(X10B-KL-Pad2)") (class "Default")
      (node (ref "X10") (pin "2") (pinfunction "KL_2") (pintype "passive"))
    )
    (net (code "96") (name "unconnected-(X11B-KL-Pad2)") (class "Default")
      (node (ref "X11") (pin "2") (pinfunction "KL_2") (pintype "passive"))
    )
    (net (code "97") (name "unconnected-(X12B-KL-Pad2)") (class "Default")
      (node (ref "X12") (pin "2") (pinfunction "KL_2") (pintype "passive"))
    )
    (net (code "98") (name "unconnected-(X13B-KL-Pad2)") (class "Default")
      (node (ref "X13") (pin "2") (pinfunction "KL_2") (pintype "passive"))
    )
    (net (code "99") (name "unconnected-(X14B-KL-Pad2)") (class "Default")
      (node (ref "X14") (pin "2") (pinfunction "KL_2") (pintype "passive"))
    )
  )
)
